# IGBT_A.net
KiCad netlist of a schematic drawn in Altium Designer
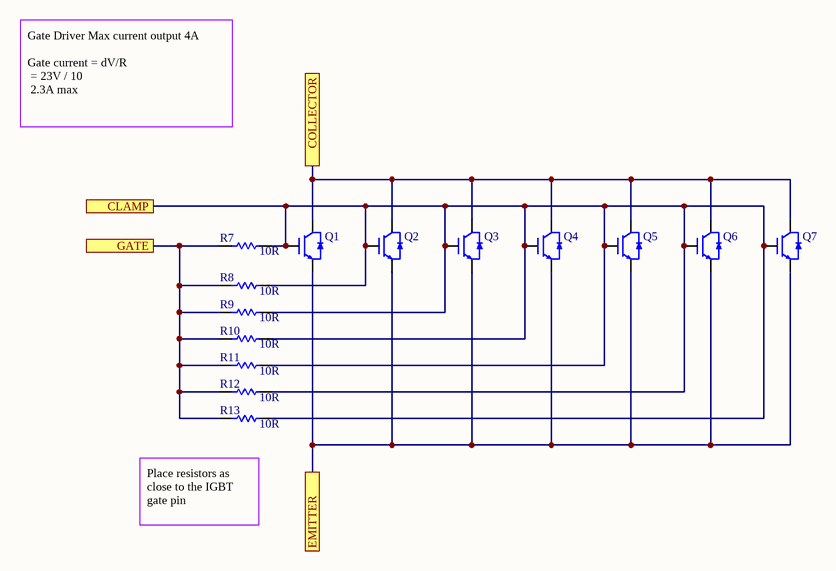
[diagram p0: IGBT_A.SchDoc]

(export (version "E")
  (design (tool "Eeschema 10.0.6"))
  (components
    (comp (ref "Q1")
      (value "STGB30V60DF")
      (footprint "DPAK2_IGBT")
      (description "IGBT 600V 60A 258W D2PAK")
      (fields (field (name "MANUFACTURER") "STMicroelectronics"))
      (libsource (lib "InverterSCHLib") (part "STGB30V60DF"))
    )
    (comp (ref "Q2")
      (value "STGB30V60DF")
      (footprint "DPAK2_IGBT")
      (description "IGBT 600V 60A 258W D2PAK")
      (fields (field (name "MANUFACTURER") "STMicroelectronics"))
      (libsource (lib "InverterSCHLib") (part "STGB30V60DF"))
    )
    (comp (ref "Q3")
      (value "STGB30V60DF")
      (footprint "DPAK2_IGBT")
      (description "IGBT 600V 60A 258W D2PAK")
      (fields (field (name "MANUFACTURER") "STMicroelectronics"))
      (libsource (lib "InverterSCHLib") (part "STGB30V60DF"))
    )
    (comp (ref "Q4")
      (value "STGB30V60DF")
      (footprint "DPAK2_IGBT")
      (description "IGBT 600V 60A 258W D2PAK")
      (fields (field (name "MANUFACTURER") "STMicroelectronics"))
      (libsource (lib "InverterSCHLib") (part "STGB30V60DF"))
    )
    (comp (ref "Q5")
      (value "STGB30V60DF")
      (footprint "DPAK2_IGBT")
      (description "IGBT 600V 60A 258W D2PAK")
      (fields (field (name "MANUFACTURER") "STMicroelectronics"))
      (libsource (lib "InverterSCHLib") (part "STGB30V60DF"))
    )
    (comp (ref "Q6")
      (value "STGB30V60DF")
      (footprint "DPAK2_IGBT")
      (description "IGBT 600V 60A 258W D2PAK")
      (fields (field (name "MANUFACTURER") "STMicroelectronics"))
      (libsource (lib "InverterSCHLib") (part "STGB30V60DF"))
    )
    (comp (ref "Q7")
      (value "STGB30V60DF")
      (footprint "DPAK2_IGBT")
      (description "IGBT 600V 60A 258W D2PAK")
      (fields (field (name "MANUFACTURER") "STMicroelectronics"))
      (libsource (lib "InverterSCHLib") (part "STGB30V60DF"))
    )
    (comp (ref "R7")
      (value "10R")
      (footprint "RES-0603")
      (description "RES SMD 10 OHM 1% 1/10W 0603")
      (fields
        (field (name "MANUFACTURER") "Yageo")
        (field (name "MANUFACTURER PART NUMBER") "RC0603FR-0710RL")
      )
      (libsource (lib "InverterSCHLib") (part "0603-10R"))
    )
    (comp (ref "R8")
      (value "10R")
      (footprint "RES-0603")
      (description "RES SMD 10 OHM 1% 1/10W 0603")
      (fields
        (field (name "MANUFACTURER") "Yageo")
        (field (name "MANUFACTURER PART NUMBER") "RC0603FR-0710RL")
      )
      (libsource (lib "InverterSCHLib") (part "0603-10R"))
    )
    (comp (ref "R9")
      (value "10R")
      (footprint "RES-0603")
      (description "RES SMD 10 OHM 1% 1/10W 0603")
      (fields
        (field (name "MANUFACTURER") "Yageo")
        (field (name "MANUFACTURER PART NUMBER") "RC0603FR-0710RL")
      )
      (libsource (lib "InverterSCHLib") (part "0603-10R"))
    )
    (comp (ref "R10")
      (value "10R")
      (footprint "RES-0603")
      (description "RES SMD 10 OHM 1% 1/10W 0603")
      (fields
        (field (name "MANUFACTURER") "Yageo")
        (field (name "MANUFACTURER PART NUMBER") "RC0603FR-0710RL")
      )
      (libsource (lib "InverterSCHLib") (part "0603-10R"))
    )
    (comp (ref "R11")
      (value "10R")
      (footprint "RES-0603")
      (description "RES SMD 10 OHM 1% 1/10W 0603")
      (fields
        (field (name "MANUFACTURER") "Yageo")
        (field (name "MANUFACTURER PART NUMBER") "RC0603FR-0710RL")
      )
      (libsource (lib "InverterSCHLib") (part "0603-10R"))
    )
    (comp (ref "R12")
      (value "10R")
      (footprint "RES-0603")
      (description "RES SMD 10 OHM 1% 1/10W 0603")
      (fields
        (field (name "MANUFACTURER") "Yageo")
        (field (name "MANUFACTURER PART NUMBER") "RC0603FR-0710RL")
      )
      (libsource (lib "InverterSCHLib") (part "0603-10R"))
    )
    (comp (ref "R13")
      (value "10R")
      (footprint "RES-0603")
      (description "RES SMD 10 OHM 1% 1/10W 0603")
      (fields
        (field (name "MANUFACTURER") "Yageo")
        (field (name "MANUFACTURER PART NUMBER") "RC0603FR-0710RL")
      )
      (libsource (lib "InverterSCHLib") (part "0603-10R"))
    )
  )
  (nets
    (net (code "1") (name "/CLAMP") (class "Default")
      (node (ref "Q1") (pin "1") (pinfunction "1_1") (pintype "passive"))
      (node (ref "Q2") (pin "1") (pinfunction "1_1") (pintype "passive"))
      (node (ref "Q3") (pin "1") (pinfunction "1_1") (pintype "passive"))
      (node (ref "Q4") (pin "1") (pinfunction "1_1") (pintype "passive"))
      (node (ref "Q5") (pin "1") (pinfunction "1_1") (pintype "passive"))
      (node (ref "Q6") (pin "1") (pinfunction "1_1") (pintype "passive"))
      (node (ref "Q7") (pin "1") (pinfunction "1_1") (pintype "passive"))
      (node (ref "R10") (pin "2") (pinfunction "2_2") (pintype "passive"))
      (node (ref "R11") (pin "2") (pinfunction "2_2") (pintype "passive"))
      (node (ref "R12") (pin "2") (pinfunction "2_2") (pintype "passive"))
      (node (ref "R13") (pin "2") (pinfunction "2_2") (pintype "passive"))
      (node (ref "R7") (pin "2") (pinfunction "2_2") (pintype "passive"))
      (node (ref "R8") (pin "2") (pinfunction "2_2") (pintype "passive"))
      (node (ref "R9") (pin "2") (pinfunction "2_2") (pintype "passive"))
    )
    (net (code "2") (name "/COLLECTOR") (class "Default")
      (node (ref "Q1") (pin "2") (pinfunction "2_2") (pintype "passive"))
      (node (ref "Q2") (pin "2") (pinfunction "2_2") (pintype "passive"))
      (node (ref "Q3") (pin "2") (pinfunction "2_2") (pintype "passive"))
      (node (ref "Q4") (pin "2") (pinfunction "2_2") (pintype "passive"))
      (node (ref "Q5") (pin "2") (pinfunction "2_2") (pintype "passive"))
      (node (ref "Q6") (pin "2") (pinfunction "2_2") (pintype "passive"))
      (node (ref "Q7") (pin "2") (pinfunction "2_2") (pintype "passive"))
    )
    (net (code "3") (name "/EMITTER") (class "Default")
      (node (ref "Q1") (pin "3") (pinfunction "3_3") (pintype "passive"))
      (node (ref "Q2") (pin "3") (pinfunction "3_3") (pintype "passive"))
      (node (ref "Q3") (pin "3") (pinfunction "3_3") (pintype "passive"))
      (node (ref "Q4") (pin "3") (pinfunction "3_3") (pintype "passive"))
      (node (ref "Q5") (pin "3") (pinfunction "3_3") (pintype "passive"))
      (node (ref "Q6") (pin "3") (pinfunction "3_3") (pintype "passive"))
      (node (ref "Q7") (pin "3") (pinfunction "3_3") (pintype "passive"))
    )
    (net (code "4") (name "/GATE") (class "Default")
      (node (ref "R10") (pin "1") (pinfunction "1_1") (pintype "passive"))
      (node (ref "R11") (pin "1") (pinfunction "1_1") (pintype "passive"))
      (node (ref "R12") (pin "1") (pinfunction "1_1") (pintype "passive"))
      (node (ref "R13") (pin "1") (pinfunction "1_1") (pintype "passive"))
      (node (ref "R7") (pin "1") (pinfunction "1_1") (pintype "passive"))
      (node (ref "R8") (pin "1") (pinfunction "1_1") (pintype "passive"))
      (node (ref "R9") (pin "1") (pinfunction "1_1") (pintype "passive"))
    )
  )
)
